# 3w-rgb-led-connector-mk-3_0.net
KiCad netlist of a schematic drawn in EAGLE
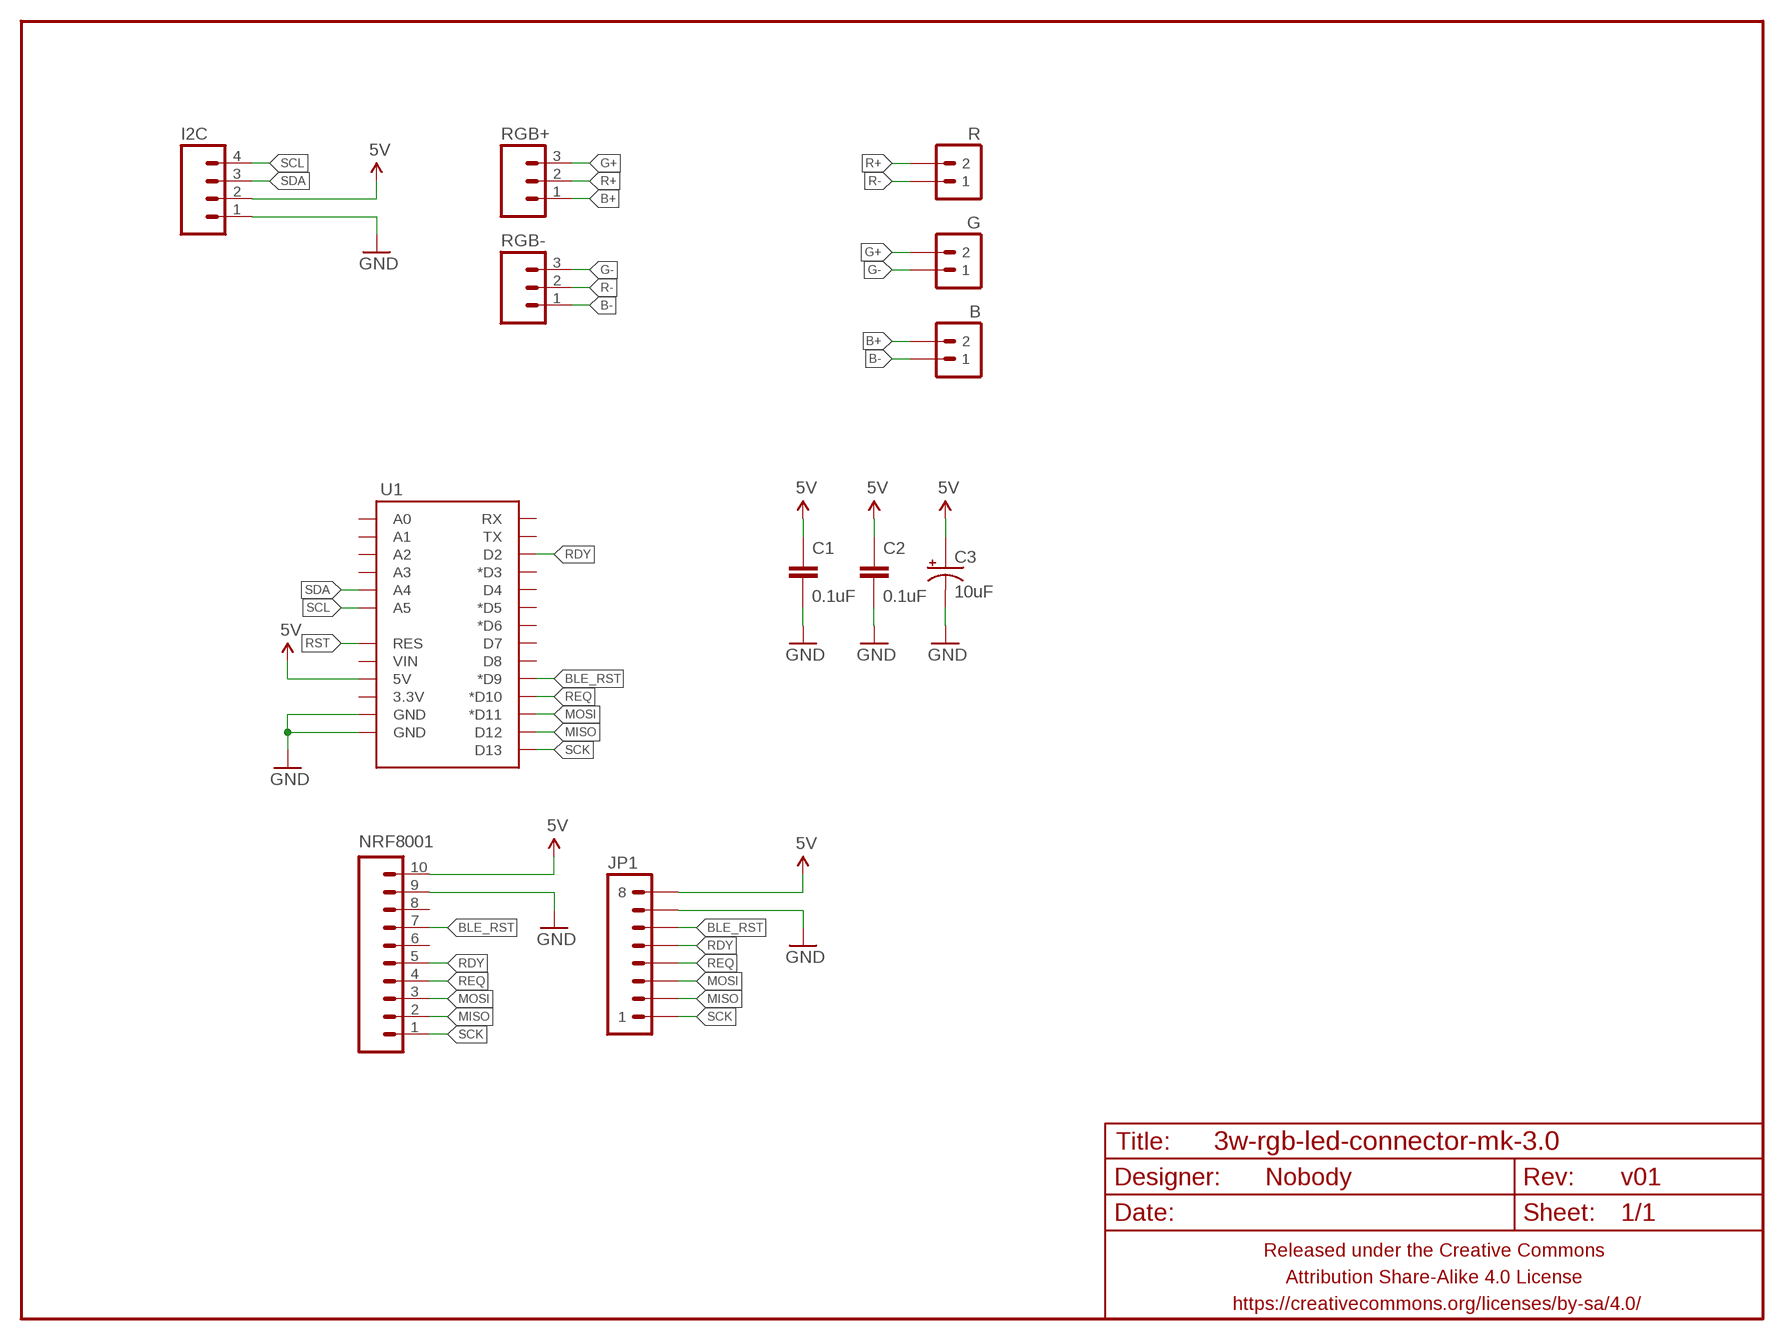
[diagram p0: schematic, sheet 1]

(export (version "E")
  (design (tool "Eeschema 10.0.6"))
  (components
    (comp (ref "B")
      (value "M023.5MM-NO_SILK")
      (footprint "eagle-import:SCREWTERMINAL-3.5MM-2-NS")
      (libsource (lib "eagle-import") (part "M023.5MM-NO_SILK"))
    )
    (comp (ref "C1")
      (value "0.1uF")
      (footprint "eagle-import:C025-024X044")
      (libsource (lib "eagle-import") (part "CAPACITOR-CERAMIC025-024X044"))
    )
    (comp (ref "C2")
      (value "0.1uF")
      (footprint "eagle-import:C025-024X044")
      (libsource (lib "eagle-import") (part "CAPACITOR-CERAMIC025-024X044"))
    )
    (comp (ref "C3")
      (value "10uF")
      (footprint "eagle-import:E2-5")
      (libsource (lib "eagle-import") (part "CAPACITOR-POLARIZEDE2-5"))
    )
    (comp (ref "FRAME1")
      (value "FRAME-LETTERNO_PACKAGE")
      (footprint "eagle-import:DUMMY")
      (fields (field (name "DESIGNER") "Nobody"))
      (libsource (lib "eagle-import") (part "FRAME-LETTERNO_PACKAGE"))
    )
    (comp (ref "G")
      (value "M023.5MM-NO_SILK")
      (footprint "eagle-import:SCREWTERMINAL-3.5MM-2-NS")
      (libsource (lib "eagle-import") (part "M023.5MM-NO_SILK"))
    )
    (comp (ref "I2C")
      (value "M04JST_XH_RA")
      (footprint "eagle-import:JST-4-XH-RA-PTH")
      (libsource (lib "eagle-import") (part "M04JST_XH_RA"))
    )
    (comp (ref "JP1")
      (value "M081X08")
      (footprint "eagle-import:1X08")
      (libsource (lib "eagle-import") (part "M081X08"))
    )
    (comp (ref "NRF8001")
      (value "M10PTH-SLIM-ASS")
      (footprint "eagle-import:1X10_PTH_SLIMASS")
      (libsource (lib "eagle-import") (part "M10PTH-SLIM-ASS"))
    )
    (comp (ref "R")
      (value "M023.5MM-NO_SILK")
      (footprint "eagle-import:SCREWTERMINAL-3.5MM-2-NS")
      (libsource (lib "eagle-import") (part "M023.5MM-NO_SILK"))
    )
    (comp (ref "RGB+")
      (value "M03JST-XH-RA-PTH")
      (footprint "eagle-import:JST-3-XH-RA-PTH")
      (libsource (lib "eagle-import") (part "M03JST-XH-RA-PTH"))
    )
    (comp (ref "RGB-")
      (value "M03JST-XH-RA-PTH")
      (footprint "eagle-import:JST-3-XH-RA-PTH")
      (libsource (lib "eagle-import") (part "M03JST-XH-RA-PTH"))
    )
    (comp (ref "U1")
      (value "ARDUINO_SHIELD_SMALLER")
      (footprint "eagle-import:ARDUINO_SHIELD_NOOUTLINE_INSIDE_SMALLER")
      (libsource (lib "eagle-import") (part "ARDUINO_SHIELD_SMALLER"))
    )
  )
  (nets
    (net (code "1") (name "5V") (class "Default")
      (node (ref "C1") (pin "1") (pinfunction "1_1") (pintype "passive"))
      (node (ref "C2") (pin "1") (pinfunction "1_1") (pintype "passive"))
      (node (ref "C3") (pin "+") (pinfunction "+_+") (pintype "passive"))
      (node (ref "I2C") (pin "2") (pinfunction "2_2") (pintype "passive"))
      (node (ref "JP1") (pin "8") (pinfunction "8_8") (pintype "passive"))
      (node (ref "NRF8001") (pin "10") (pinfunction "10_10") (pintype "passive"))
      (node (ref "U1") (pin "5V") (pinfunction "5V_5V") (pintype "bidirectional"))
    )
    (net (code "2") (name "B+") (class "Default")
      (node (ref "B") (pin "2") (pinfunction "2_2") (pintype "passive"))
      (node (ref "RGB+") (pin "1") (pinfunction "1_1") (pintype "passive"))
    )
    (net (code "3") (name "B-") (class "Default")
      (node (ref "B") (pin "1") (pinfunction "1_1") (pintype "passive"))
      (node (ref "RGB-") (pin "1") (pinfunction "1_1") (pintype "passive"))
    )
    (net (code "4") (name "BLE_RST") (class "Default")
      (node (ref "JP1") (pin "6") (pinfunction "6_6") (pintype "passive"))
      (node (ref "NRF8001") (pin "7") (pinfunction "7_7") (pintype "passive"))
      (node (ref "U1") (pin "D9") (pinfunction "*D9_D9") (pintype "bidirectional"))
    )
    (net (code "5") (name "G+") (class "Default")
      (node (ref "G") (pin "2") (pinfunction "2_2") (pintype "passive"))
      (node (ref "RGB+") (pin "3") (pinfunction "3_3") (pintype "passive"))
    )
    (net (code "6") (name "G-") (class "Default")
      (node (ref "G") (pin "1") (pinfunction "1_1") (pintype "passive"))
      (node (ref "RGB-") (pin "3") (pinfunction "3_3") (pintype "passive"))
    )
    (net (code "7") (name "GND") (class "Default")
      (node (ref "C1") (pin "2") (pinfunction "2_2") (pintype "passive"))
      (node (ref "C2") (pin "2") (pinfunction "2_2") (pintype "passive"))
      (node (ref "C3") (pin "-") (pinfunction "-_-") (pintype "passive"))
      (node (ref "I2C") (pin "1") (pinfunction "1_1") (pintype "passive"))
      (node (ref "JP1") (pin "7") (pinfunction "7_7") (pintype "passive"))
      (node (ref "NRF8001") (pin "9") (pinfunction "9_9") (pintype "passive"))
      (node (ref "U1") (pin "GND@0") (pinfunction "GND_GND@0") (pintype "bidirectional"))
      (node (ref "U1") (pin "GND@1") (pinfunction "GND_GND@1") (pintype "bidirectional"))
    )
    (net (code "8") (name "MISO") (class "Default")
      (node (ref "JP1") (pin "2") (pinfunction "2_2") (pintype "passive"))
      (node (ref "NRF8001") (pin "2") (pinfunction "2_2") (pintype "passive"))
      (node (ref "U1") (pin "D12") (pinfunction "D12_D12") (pintype "bidirectional"))
    )
    (net (code "9") (name "MOSI") (class "Default")
      (node (ref "JP1") (pin "3") (pinfunction "3_3") (pintype "passive"))
      (node (ref "NRF8001") (pin "3") (pinfunction "3_3") (pintype "passive"))
      (node (ref "U1") (pin "D11") (pinfunction "*D11_D11") (pintype "bidirectional"))
    )
    (net (code "10") (name "R+") (class "Default")
      (node (ref "R") (pin "2") (pinfunction "2_2") (pintype "passive"))
      (node (ref "RGB+") (pin "2") (pinfunction "2_2") (pintype "passive"))
    )
    (net (code "11") (name "R-") (class "Default")
      (node (ref "R") (pin "1") (pinfunction "1_1") (pintype "passive"))
      (node (ref "RGB-") (pin "2") (pinfunction "2_2") (pintype "passive"))
    )
    (net (code "12") (name "RDY") (class "Default")
      (node (ref "JP1") (pin "5") (pinfunction "5_5") (pintype "passive"))
      (node (ref "NRF8001") (pin "5") (pinfunction "5_5") (pintype "passive"))
      (node (ref "U1") (pin "D2") (pinfunction "D2_D2") (pintype "bidirectional"))
    )
    (net (code "13") (name "REQ") (class "Default")
      (node (ref "JP1") (pin "4") (pinfunction "4_4") (pintype "passive"))
      (node (ref "NRF8001") (pin "4") (pinfunction "4_4") (pintype "passive"))
      (node (ref "U1") (pin "D10") (pinfunction "*D10_D10") (pintype "bidirectional"))
    )
    (net (code "14") (name "RST") (class "Default")
      (node (ref "U1") (pin "RES") (pinfunction "RES_RES") (pintype "bidirectional"))
    )
    (net (code "15") (name "SCK") (class "Default")
      (node (ref "JP1") (pin "1") (pinfunction "1_1") (pintype "passive"))
      (node (ref "NRF8001") (pin "1") (pinfunction "1_1") (pintype "passive"))
      (node (ref "U1") (pin "D13") (pinfunction "D13_D13") (pintype "bidirectional"))
    )
    (net (code "16") (name "SCL") (class "Default")
      (node (ref "I2C") (pin "4") (pinfunction "4_4") (pintype "passive"))
      (node (ref "U1") (pin "A5") (pinfunction "A5_A5") (pintype "bidirectional"))
    )
    (net (code "17") (name "SDA") (class "Default")
      (node (ref "I2C") (pin "3") (pinfunction "3_3") (pintype "passive"))
      (node (ref "U1") (pin "A4") (pinfunction "A4_A4") (pintype "bidirectional"))
    )
    (net (code "18") (name "unconnected-(NRF8001-Pad6)") (class "Default")
      (node (ref "NRF8001") (pin "6") (pinfunction "6_6") (pintype "passive"))
    )
    (net (code "19") (name "unconnected-(NRF8001-Pad8)") (class "Default")
      (node (ref "NRF8001") (pin "8") (pinfunction "8_8") (pintype "passive"))
    )
    (net (code "20") (name "unconnected-(U1-*D3-PadD3)") (class "Default")
      (node (ref "U1") (pin "D3") (pinfunction "*D3_D3") (pintype "bidirectional"))
    )
    (net (code "21") (name "unconnected-(U1-*D5-PadD5)") (class "Default")
      (node (ref "U1") (pin "D5") (pinfunction "*D5_D5") (pintype "bidirectional"))
    )
    (net (code "22") (name "unconnected-(U1-*D6-PadD6)") (class "Default")
      (node (ref "U1") (pin "D6") (pinfunction "*D6_D6") (pintype "bidirectional"))
    )
    (net (code "23") (name "unconnected-(U1-Pad3.3V)") (class "Default")
      (node (ref "U1") (pin "3.3V") (pinfunction "3.3V_3.3V") (pintype "bidirectional"))
    )
    (net (code "24") (name "unconnected-(U1-PadA0)") (class "Default")
      (node (ref "U1") (pin "A0") (pinfunction "A0_A0") (pintype "bidirectional"))
    )
    (net (code "25") (name "unconnected-(U1-PadA1)") (class "Default")
      (node (ref "U1") (pin "A1") (pinfunction "A1_A1") (pintype "bidirectional"))
    )
    (net (code "26") (name "unconnected-(U1-PadA2)") (class "Default")
      (node (ref "U1") (pin "A2") (pinfunction "A2_A2") (pintype "bidirectional"))
    )
    (net (code "27") (name "unconnected-(U1-PadA3)") (class "Default")
      (node (ref "U1") (pin "A3") (pinfunction "A3_A3") (pintype "bidirectional"))
    )
    (net (code "28") (name "unconnected-(U1-PadD4)") (class "Default")
      (node (ref "U1") (pin "D4") (pinfunction "D4_D4") (pintype "bidirectional"))
    )
    (net (code "29") (name "unconnected-(U1-PadD7)") (class "Default")
      (node (ref "U1") (pin "D7") (pinfunction "D7_D7") (pintype "bidirectional"))
    )
    (net (code "30") (name "unconnected-(U1-PadD8)") (class "Default")
      (node (ref "U1") (pin "D8") (pinfunction "D8_D8") (pintype "bidirectional"))
    )
    (net (code "31") (name "unconnected-(U1-PadRX)") (class "Default")
      (node (ref "U1") (pin "RX") (pinfunction "RX_RX") (pintype "bidirectional"))
    )
    (net (code "32") (name "unconnected-(U1-PadTX)") (class "Default")
      (node (ref "U1") (pin "TX") (pinfunction "TX_TX") (pintype "bidirectional"))
    )
    (net (code "33") (name "unconnected-(U1-PadVIN)") (class "Default")
      (node (ref "U1") (pin "VIN") (pinfunction "VIN_VIN") (pintype "bidirectional"))
    )
  )
)
